# anemo5.net
KiCad netlist of a schematic drawn in EAGLE
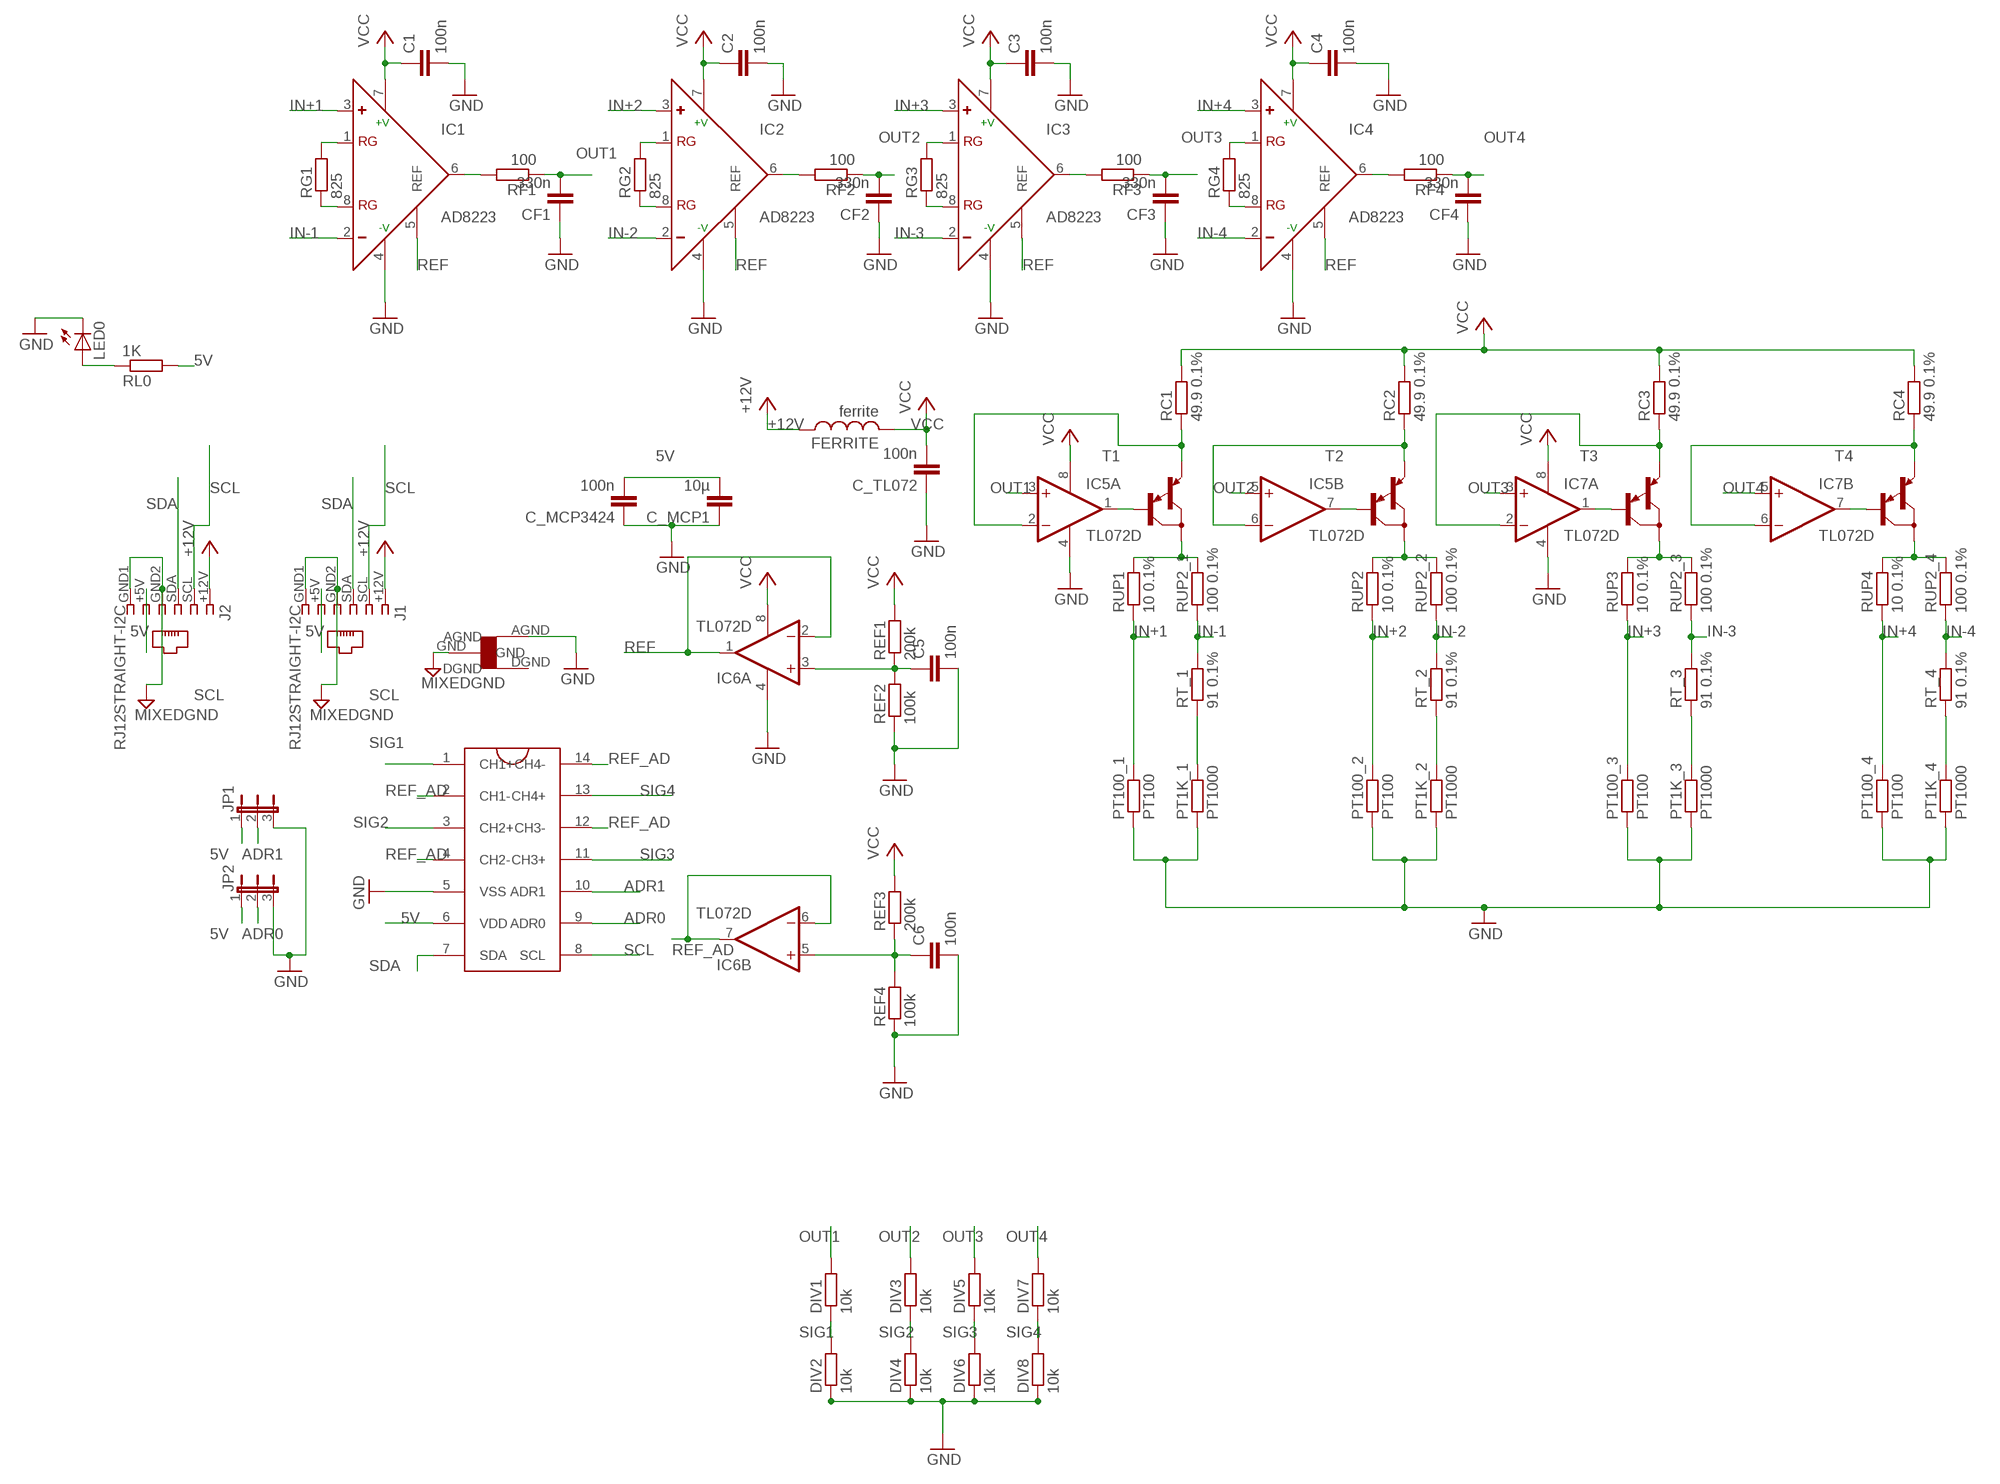
[diagram p0: schematic, sheet 1]

(export (version "E")
  (design (tool "Eeschema 10.0.6"))
  (components
    (comp (ref "C1")
      (value "100n")
      (footprint "eagle-import:C1206")
      (libsource (lib "eagle-import") (part "C-EUC1206"))
    )
    (comp (ref "C2")
      (value "100n")
      (footprint "eagle-import:C1206")
      (libsource (lib "eagle-import") (part "C-EUC1206"))
    )
    (comp (ref "C3")
      (value "100n")
      (footprint "eagle-import:C1206")
      (libsource (lib "eagle-import") (part "C-EUC1206"))
    )
    (comp (ref "C4")
      (value "100n")
      (footprint "eagle-import:C1206")
      (libsource (lib "eagle-import") (part "C-EUC1206"))
    )
    (comp (ref "C5")
      (value "100n")
      (footprint "eagle-import:C1206")
      (libsource (lib "eagle-import") (part "C-EUC1206"))
    )
    (comp (ref "C6")
      (value "100n")
      (footprint "eagle-import:C1206")
      (libsource (lib "eagle-import") (part "C-EUC1206"))
    )
    (comp (ref "CF1")
      (value "330n")
      (footprint "eagle-import:C1206")
      (libsource (lib "eagle-import") (part "C-EUC1206"))
    )
    (comp (ref "CF2")
      (value "330n")
      (footprint "eagle-import:C1206")
      (libsource (lib "eagle-import") (part "C-EUC1206"))
    )
    (comp (ref "CF3")
      (value "330n")
      (footprint "eagle-import:C1206")
      (libsource (lib "eagle-import") (part "C-EUC1206"))
    )
    (comp (ref "CF4")
      (value "330n")
      (footprint "eagle-import:C1206")
      (libsource (lib "eagle-import") (part "C-EUC1206"))
    )
    (comp (ref "C_MCP1")
      (value "10µ")
      (footprint "eagle-import:C1206")
      (libsource (lib "eagle-import") (part "C-EUC1206"))
    )
    (comp (ref "C_MCP3424")
      (value "100n")
      (footprint "eagle-import:C1206")
      (libsource (lib "eagle-import") (part "C-EUC1206"))
    )
    (comp (ref "C_TL072")
      (value "100n")
      (footprint "eagle-import:C1206")
      (libsource (lib "eagle-import") (part "C-EUC1206"))
    )
    (comp (ref "DIV1")
      (value "10k")
      (footprint "eagle-import:M1206")
      (libsource (lib "eagle-import") (part "R-EU_M1206"))
    )
    (comp (ref "DIV2")
      (value "10k")
      (footprint "eagle-import:M1206")
      (libsource (lib "eagle-import") (part "R-EU_M1206"))
    )
    (comp (ref "DIV3")
      (value "10k")
      (footprint "eagle-import:M1206")
      (libsource (lib "eagle-import") (part "R-EU_M1206"))
    )
    (comp (ref "DIV4")
      (value "10k")
      (footprint "eagle-import:M1206")
      (libsource (lib "eagle-import") (part "R-EU_M1206"))
    )
    (comp (ref "DIV5")
      (value "10k")
      (footprint "eagle-import:M1206")
      (libsource (lib "eagle-import") (part "R-EU_M1206"))
    )
    (comp (ref "DIV6")
      (value "10k")
      (footprint "eagle-import:M1206")
      (libsource (lib "eagle-import") (part "R-EU_M1206"))
    )
    (comp (ref "DIV7")
      (value "10k")
      (footprint "eagle-import:M1206")
      (libsource (lib "eagle-import") (part "R-EU_M1206"))
    )
    (comp (ref "DIV8")
      (value "10k")
      (footprint "eagle-import:M1206")
      (libsource (lib "eagle-import") (part "R-EU_M1206"))
    )
    (comp (ref "FERRITE")
      (value "ferrite")
      (footprint "eagle-import:L3216C")
      (libsource (lib "eagle-import") (part "L-USL3216C"))
    )
    (comp (ref "IC1")
      (value "AD8223")
      (footprint "eagle-import:SO8")
      (fields (field (name "MPN") "AD620AR"))
      (libsource (lib "eagle-import") (part "AD620R"))
    )
    (comp (ref "IC2")
      (value "AD8223")
      (footprint "eagle-import:SO8")
      (fields (field (name "MPN") "AD620AR"))
      (libsource (lib "eagle-import") (part "AD620R"))
    )
    (comp (ref "IC3")
      (value "AD8223")
      (footprint "eagle-import:SO8")
      (fields (field (name "MPN") "AD620AR"))
      (libsource (lib "eagle-import") (part "AD620R"))
    )
    (comp (ref "IC4")
      (value "AD8223")
      (footprint "eagle-import:SO8")
      (fields (field (name "MPN") "AD620AR"))
      (libsource (lib "eagle-import") (part "AD620R"))
    )
    (comp (ref "IC5")
      (value "TL072D")
      (footprint "eagle-import:SO08")
      (libsource (lib "eagle-import") (part "TL072D"))
    )
    (comp (ref "IC6")
      (value "TL072D")
      (footprint "eagle-import:SO08")
      (libsource (lib "eagle-import") (part "TL072D"))
    )
    (comp (ref "IC7")
      (value "TL072D")
      (footprint "eagle-import:SO08")
      (libsource (lib "eagle-import") (part "TL072D"))
    )
    (comp (ref "J1")
      (value "RJ12STRAIGHT-I2C")
      (footprint "eagle-import:RJ12-STRAIGHT-I2C")
      (libsource (lib "eagle-import") (part "RJ12STRAIGHT-I2C"))
    )
    (comp (ref "J2")
      (value "RJ12STRAIGHT-I2C")
      (footprint "eagle-import:RJ12-STRAIGHT-I2C")
      (libsource (lib "eagle-import") (part "RJ12STRAIGHT-I2C"))
    )
    (comp (ref "JP1")
      (value "JP2E")
      (footprint "eagle-import:JP2")
      (libsource (lib "eagle-import") (part "JP2E"))
    )
    (comp (ref "JP2")
      (value "JP2E")
      (footprint "eagle-import:JP2")
      (libsource (lib "eagle-import") (part "JP2E"))
    )
    (comp (ref "LED0")
      (value "LED1206")
      (footprint "eagle-import:LED-1206")
      (libsource (lib "eagle-import") (part "LED1206"))
    )
    (comp (ref "PT1K_1")
      (value "PT1000")
      (footprint "eagle-import:M1206")
      (libsource (lib "eagle-import") (part "R-EU_M1206"))
    )
    (comp (ref "PT1K_2")
      (value "PT1000")
      (footprint "eagle-import:M1206")
      (libsource (lib "eagle-import") (part "R-EU_M1206"))
    )
    (comp (ref "PT1K_3")
      (value "PT1000")
      (footprint "eagle-import:M1206")
      (libsource (lib "eagle-import") (part "R-EU_M1206"))
    )
    (comp (ref "PT1K_4")
      (value "PT1000")
      (footprint "eagle-import:M1206")
      (libsource (lib "eagle-import") (part "R-EU_M1206"))
    )
    (comp (ref "PT100_1")
      (value "PT100")
      (footprint "eagle-import:M1206")
      (libsource (lib "eagle-import") (part "R-EU_M1206"))
    )
    (comp (ref "PT100_2")
      (value "PT100")
      (footprint "eagle-import:M1206")
      (libsource (lib "eagle-import") (part "R-EU_M1206"))
    )
    (comp (ref "PT100_3")
      (value "PT100")
      (footprint "eagle-import:M1206")
      (libsource (lib "eagle-import") (part "R-EU_M1206"))
    )
    (comp (ref "PT100_4")
      (value "PT100")
      (footprint "eagle-import:M1206")
      (libsource (lib "eagle-import") (part "R-EU_M1206"))
    )
    (comp (ref "RC1")
      (value "49.9 0.1%")
      (footprint "eagle-import:M1206")
      (libsource (lib "eagle-import") (part "R-EU_M1206"))
    )
    (comp (ref "RC2")
      (value "49.9 0.1%")
      (footprint "eagle-import:M1206")
      (libsource (lib "eagle-import") (part "R-EU_M1206"))
    )
    (comp (ref "RC3")
      (value "49.9 0.1%")
      (footprint "eagle-import:M1206")
      (libsource (lib "eagle-import") (part "R-EU_M1206"))
    )
    (comp (ref "RC4")
      (value "49.9 0.1%")
      (footprint "eagle-import:M1206")
      (libsource (lib "eagle-import") (part "R-EU_M1206"))
    )
    (comp (ref "REF1")
      (value "200k")
      (footprint "eagle-import:M1206")
      (libsource (lib "eagle-import") (part "R-EU_M1206"))
    )
    (comp (ref "REF2")
      (value "100k")
      (footprint "eagle-import:M1206")
      (libsource (lib "eagle-import") (part "R-EU_M1206"))
    )
    (comp (ref "REF3")
      (value "200k")
      (footprint "eagle-import:M1206")
      (libsource (lib "eagle-import") (part "R-EU_M1206"))
    )
    (comp (ref "REF4")
      (value "100k")
      (footprint "eagle-import:M1206")
      (libsource (lib "eagle-import") (part "R-EU_M1206"))
    )
    (comp (ref "RF1")
      (value "100")
      (footprint "eagle-import:M1206")
      (libsource (lib "eagle-import") (part "R-EU_M1206"))
    )
    (comp (ref "RF2")
      (value "100")
      (footprint "eagle-import:M1206")
      (libsource (lib "eagle-import") (part "R-EU_M1206"))
    )
    (comp (ref "RF3")
      (value "100")
      (footprint "eagle-import:M1206")
      (libsource (lib "eagle-import") (part "R-EU_M1206"))
    )
    (comp (ref "RF4")
      (value "100")
      (footprint "eagle-import:M1206")
      (libsource (lib "eagle-import") (part "R-EU_M1206"))
    )
    (comp (ref "RG1")
      (value "825")
      (footprint "eagle-import:M1206")
      (libsource (lib "eagle-import") (part "R-EU_M1206"))
    )
    (comp (ref "RG2")
      (value "825")
      (footprint "eagle-import:M1206")
      (libsource (lib "eagle-import") (part "R-EU_M1206"))
    )
    (comp (ref "RG3")
      (value "825")
      (footprint "eagle-import:M1206")
      (libsource (lib "eagle-import") (part "R-EU_M1206"))
    )
    (comp (ref "RG4")
      (value "825")
      (footprint "eagle-import:M1206")
      (libsource (lib "eagle-import") (part "R-EU_M1206"))
    )
    (comp (ref "RL0")
      (value "1K")
      (footprint "eagle-import:M1206")
      (libsource (lib "eagle-import") (part "R-EU_M1206"))
    )
    (comp (ref "RT_1")
      (value "91 0.1%")
      (footprint "eagle-import:M1206")
      (libsource (lib "eagle-import") (part "R-EU_M1206"))
    )
    (comp (ref "RT_2")
      (value "91 0.1%")
      (footprint "eagle-import:M1206")
      (libsource (lib "eagle-import") (part "R-EU_M1206"))
    )
    (comp (ref "RT_3")
      (value "91 0.1%")
      (footprint "eagle-import:M1206")
      (libsource (lib "eagle-import") (part "R-EU_M1206"))
    )
    (comp (ref "RT_4")
      (value "91 0.1%")
      (footprint "eagle-import:M1206")
      (libsource (lib "eagle-import") (part "R-EU_M1206"))
    )
    (comp (ref "RUP1")
      (value "10 0.1%")
      (footprint "eagle-import:M1206")
      (libsource (lib "eagle-import") (part "R-EU_M1206"))
    )
    (comp (ref "RUP2")
      (value "10 0.1%")
      (footprint "eagle-import:M1206")
      (libsource (lib "eagle-import") (part "R-EU_M1206"))
    )
    (comp (ref "RUP2_1")
      (value "100 0.1%")
      (footprint "eagle-import:M1206")
      (libsource (lib "eagle-import") (part "R-EU_M1206"))
    )
    (comp (ref "RUP2_2")
      (value "100 0.1%")
      (footprint "eagle-import:M1206")
      (libsource (lib "eagle-import") (part "R-EU_M1206"))
    )
    (comp (ref "RUP2_3")
      (value "100 0.1%")
      (footprint "eagle-import:M1206")
      (libsource (lib "eagle-import") (part "R-EU_M1206"))
    )
    (comp (ref "RUP2_4")
      (value "100 0.1%")
      (footprint "eagle-import:M1206")
      (libsource (lib "eagle-import") (part "R-EU_M1206"))
    )
    (comp (ref "RUP3")
      (value "10 0.1%")
      (footprint "eagle-import:M1206")
      (libsource (lib "eagle-import") (part "R-EU_M1206"))
    )
    (comp (ref "RUP4")
      (value "10 0.1%")
      (footprint "eagle-import:M1206")
      (libsource (lib "eagle-import") (part "R-EU_M1206"))
    )
    (comp (ref "T1")
      (value "MMBTA64LT1-PNP_DARL-SOT23-BEC")
      (footprint "eagle-import:SOT23-BEC")
      (libsource (lib "eagle-import") (part "-PNP_DARL-SOT23-BECMMBTA64LT1"))
    )
    (comp (ref "T2")
      (value "MMBTA64LT1-PNP_DARL-SOT23-BEC")
      (footprint "eagle-import:SOT23-BEC")
      (libsource (lib "eagle-import") (part "-PNP_DARL-SOT23-BECMMBTA64LT1"))
    )
    (comp (ref "T3")
      (value "MMBTA64LT1-PNP_DARL-SOT23-BEC")
      (footprint "eagle-import:SOT23-BEC")
      (libsource (lib "eagle-import") (part "-PNP_DARL-SOT23-BECMMBTA64LT1"))
    )
    (comp (ref "T4")
      (value "MMBTA64LT1-PNP_DARL-SOT23-BEC")
      (footprint "eagle-import:SOT23-BEC")
      (libsource (lib "eagle-import") (part "-PNP_DARL-SOT23-BECMMBTA64LT1"))
    )
    (comp (ref "U$1")
      (value "MCP3424(SO14)")
      (footprint "eagle-import:14LDSOIC")
      (libsource (lib "eagle-import") (part "MCP3424(SO14)"))
    )
    (comp (ref "U$2")
      (value "STARGND")
      (footprint "eagle-import:STAR")
      (libsource (lib "eagle-import") (part "STARGND"))
    )
  )
  (nets
    (net (code "1") (name "+12V") (class "Default")
      (node (ref "FERRITE") (pin "1") (pinfunction "1_1") (pintype "passive"))
      (node (ref "J1") (pin "+12V") (pinfunction "1_+12V") (pintype "bidirectional"))
      (node (ref "J2") (pin "+12V") (pinfunction "1_+12V") (pintype "bidirectional"))
    )
    (net (code "2") (name "/5V") (class "Default")
      (node (ref "C_MCP1") (pin "2") (pinfunction "2_2") (pintype "passive"))
      (node (ref "C_MCP3424") (pin "2") (pinfunction "2_2") (pintype "passive"))
      (node (ref "J1") (pin "+5V") (pinfunction "5_+5V") (pintype "bidirectional"))
      (node (ref "J2") (pin "+5V") (pinfunction "5_+5V") (pintype "bidirectional"))
      (node (ref "JP1") (pin "1") (pinfunction "1_1") (pintype "passive"))
      (node (ref "JP2") (pin "1") (pinfunction "1_1") (pintype "passive"))
      (node (ref "RL0") (pin "2") (pinfunction "2_2") (pintype "passive"))
      (node (ref "U$1") (pin "6") (pinfunction "VDD_6") (pintype "bidirectional"))
    )
    (net (code "3") (name "/ADR0") (class "Default")
      (node (ref "JP2") (pin "2") (pinfunction "2_2") (pintype "passive"))
      (node (ref "U$1") (pin "9") (pinfunction "ADR0_9") (pintype "bidirectional"))
    )
    (net (code "4") (name "/ADR1") (class "Default")
      (node (ref "JP1") (pin "2") (pinfunction "2_2") (pintype "passive"))
      (node (ref "U$1") (pin "10") (pinfunction "ADR1_10") (pintype "bidirectional"))
    )
    (net (code "5") (name "/IN+1") (class "Default")
      (node (ref "IC1") (pin "3") (pinfunction "+_3") (pintype "input"))
      (node (ref "PT100_1") (pin "2") (pinfunction "2_2") (pintype "passive"))
      (node (ref "RUP1") (pin "1") (pinfunction "1_1") (pintype "passive"))
    )
    (net (code "6") (name "/IN+2") (class "Default")
      (node (ref "IC2") (pin "3") (pinfunction "+_3") (pintype "input"))
      (node (ref "PT100_2") (pin "2") (pinfunction "2_2") (pintype "passive"))
      (node (ref "RUP2") (pin "1") (pinfunction "1_1") (pintype "passive"))
    )
    (net (code "7") (name "/IN+3") (class "Default")
      (node (ref "IC3") (pin "3") (pinfunction "+_3") (pintype "input"))
      (node (ref "PT100_3") (pin "2") (pinfunction "2_2") (pintype "passive"))
      (node (ref "RUP3") (pin "1") (pinfunction "1_1") (pintype "passive"))
    )
    (net (code "8") (name "/IN+4") (class "Default")
      (node (ref "IC4") (pin "3") (pinfunction "+_3") (pintype "input"))
      (node (ref "PT100_4") (pin "2") (pinfunction "2_2") (pintype "passive"))
      (node (ref "RUP4") (pin "1") (pinfunction "1_1") (pintype "passive"))
    )
    (net (code "9") (name "/IN-1") (class "Default")
      (node (ref "IC1") (pin "2") (pinfunction "-_2") (pintype "input"))
      (node (ref "RT_1") (pin "2") (pinfunction "2_2") (pintype "passive"))
      (node (ref "RUP2_1") (pin "1") (pinfunction "1_1") (pintype "passive"))
    )
    (net (code "10") (name "/IN-2") (class "Default")
      (node (ref "IC2") (pin "2") (pinfunction "-_2") (pintype "input"))
      (node (ref "RT_2") (pin "2") (pinfunction "2_2") (pintype "passive"))
      (node (ref "RUP2_2") (pin "1") (pinfunction "1_1") (pintype "passive"))
    )
    (net (code "11") (name "/IN-3") (class "Default")
      (node (ref "IC3") (pin "2") (pinfunction "-_2") (pintype "input"))
      (node (ref "RT_3") (pin "2") (pinfunction "2_2") (pintype "passive"))
      (node (ref "RUP2_3") (pin "1") (pinfunction "1_1") (pintype "passive"))
    )
    (net (code "12") (name "/IN-4") (class "Default")
      (node (ref "IC4") (pin "2") (pinfunction "-_2") (pintype "input"))
      (node (ref "RT_4") (pin "2") (pinfunction "2_2") (pintype "passive"))
      (node (ref "RUP2_4") (pin "1") (pinfunction "1_1") (pintype "passive"))
    )
    (net (code "13") (name "/OUT1") (class "Default")
      (node (ref "CF1") (pin "2") (pinfunction "2_2") (pintype "passive"))
      (node (ref "DIV1") (pin "2") (pinfunction "2_2") (pintype "passive"))
      (node (ref "IC5") (pin "3") (pinfunction "+IN_3") (pintype "input"))
      (node (ref "RF1") (pin "1") (pinfunction "1_1") (pintype "passive"))
    )
    (net (code "14") (name "/OUT2") (class "Default")
      (node (ref "CF2") (pin "2") (pinfunction "2_2") (pintype "passive"))
      (node (ref "DIV3") (pin "2") (pinfunction "2_2") (pintype "passive"))
      (node (ref "IC5") (pin "5") (pinfunction "+IN_5") (pintype "input"))
      (node (ref "RF2") (pin "1") (pinfunction "1_1") (pintype "passive"))
    )
    (net (code "15") (name "/OUT3") (class "Default")
      (node (ref "CF3") (pin "2") (pinfunction "2_2") (pintype "passive"))
      (node (ref "DIV5") (pin "2") (pinfunction "2_2") (pintype "passive"))
      (node (ref "IC7") (pin "3") (pinfunction "+IN_3") (pintype "input"))
      (node (ref "RF3") (pin "1") (pinfunction "1_1") (pintype "passive"))
    )
    (net (code "16") (name "/OUT4") (class "Default")
      (node (ref "CF4") (pin "2") (pinfunction "2_2") (pintype "passive"))
      (node (ref "DIV7") (pin "2") (pinfunction "2_2") (pintype "passive"))
      (node (ref "IC7") (pin "5") (pinfunction "+IN_5") (pintype "input"))
      (node (ref "RF4") (pin "1") (pinfunction "1_1") (pintype "passive"))
    )
    (net (code "17") (name "/REF") (class "Default")
      (node (ref "IC1") (pin "5") (pinfunction "REF_5") (pintype "passive"))
      (node (ref "IC2") (pin "5") (pinfunction "REF_5") (pintype "passive"))
      (node (ref "IC3") (pin "5") (pinfunction "REF_5") (pintype "passive"))
      (node (ref "IC4") (pin "5") (pinfunction "REF_5") (pintype "passive"))
      (node (ref "IC6") (pin "1") (pinfunction "OUT_1") (pintype "output"))
      (node (ref "IC6") (pin "2") (pinfunction "-IN_2") (pintype "input"))
    )
    (net (code "18") (name "/REF_AD") (class "Default")
      (node (ref "IC6") (pin "6") (pinfunction "-IN_6") (pintype "input"))
      (node (ref "IC6") (pin "7") (pinfunction "OUT_7") (pintype "output"))
      (node (ref "U$1") (pin "12") (pinfunction "CH3-_12") (pintype "bidirectional"))
      (node (ref "U$1") (pin "14") (pinfunction "CH4-_14") (pintype "bidirectional"))
      (node (ref "U$1") (pin "2") (pinfunction "CH1-_2") (pintype "bidirectional"))
      (node (ref "U$1") (pin "4") (pinfunction "CH2-_4") (pintype "bidirectional"))
    )
    (net (code "19") (name "/SCL") (class "Default")
      (node (ref "J1") (pin "SCL") (pinfunction "2_SCL") (pintype "bidirectional"))
      (node (ref "J2") (pin "SCL") (pinfunction "2_SCL") (pintype "bidirectional"))
      (node (ref "U$1") (pin "8") (pinfunction "SCL_8") (pintype "bidirectional"))
    )
    (net (code "20") (name "/SDA") (class "Default")
      (node (ref "J1") (pin "SDA") (pinfunction "3_SDA") (pintype "bidirectional"))
      (node (ref "J2") (pin "SDA") (pinfunction "3_SDA") (pintype "bidirectional"))
      (node (ref "U$1") (pin "7") (pinfunction "SDA_7") (pintype "bidirectional"))
    )
    (net (code "21") (name "/SIG1") (class "Default")
      (node (ref "DIV1") (pin "1") (pinfunction "1_1") (pintype "passive"))
      (node (ref "DIV2") (pin "2") (pinfunction "2_2") (pintype "passive"))
      (node (ref "U$1") (pin "1") (pinfunction "CH1+_1") (pintype "bidirectional"))
    )
    (net (code "22") (name "/SIG2") (class "Default")
      (node (ref "DIV3") (pin "1") (pinfunction "1_1") (pintype "passive"))
      (node (ref "DIV4") (pin "2") (pinfunction "2_2") (pintype "passive"))
      (node (ref "U$1") (pin "3") (pinfunction "CH2+_3") (pintype "bidirectional"))
    )
    (net (code "23") (name "/SIG3") (class "Default")
      (node (ref "DIV5") (pin "1") (pinfunction "1_1") (pintype "passive"))
      (node (ref "DIV6") (pin "2") (pinfunction "2_2") (pintype "passive"))
      (node (ref "U$1") (pin "11") (pinfunction "CH3+_11") (pintype "bidirectional"))
    )
    (net (code "24") (name "/SIG4") (class "Default")
      (node (ref "DIV7") (pin "1") (pinfunction "1_1") (pintype "passive"))
      (node (ref "DIV8") (pin "2") (pinfunction "2_2") (pintype "passive"))
      (node (ref "U$1") (pin "13") (pinfunction "CH4+_13") (pintype "bidirectional"))
    )
    (net (code "25") (name "GND") (class "Default")
      (node (ref "C1") (pin "2") (pinfunction "2_2") (pintype "passive"))
      (node (ref "C2") (pin "2") (pinfunction "2_2") (pintype "passive"))
      (node (ref "C3") (pin "2") (pinfunction "2_2") (pintype "passive"))
      (node (ref "C4") (pin "2") (pinfunction "2_2") (pintype "passive"))
      (node (ref "C5") (pin "2") (pinfunction "2_2") (pintype "passive"))
      (node (ref "C6") (pin "2") (pinfunction "2_2") (pintype "passive"))
      (node (ref "CF1") (pin "1") (pinfunction "1_1") (pintype "passive"))
      (node (ref "CF2") (pin "1") (pinfunction "1_1") (pintype "passive"))
      (node (ref "CF3") (pin "1") (pinfunction "1_1") (pintype "passive"))
      (node (ref "CF4") (pin "1") (pinfunction "1_1") (pintype "passive"))
      (node (ref "C_MCP1") (pin "1") (pinfunction "1_1") (pintype "passive"))
      (node (ref "C_MCP3424") (pin "1") (pinfunction "1_1") (pintype "passive"))
      (node (ref "C_TL072") (pin "1") (pinfunction "1_1") (pintype "passive"))
      (node (ref "DIV2") (pin "1") (pinfunction "1_1") (pintype "passive"))
      (node (ref "DIV4") (pin "1") (pinfunction "1_1") (pintype "passive"))
      (node (ref "DIV6") (pin "1") (pinfunction "1_1") (pintype "passive"))
      (node (ref "DIV8") (pin "1") (pinfunction "1_1") (pintype "passive"))
      (node (ref "IC1") (pin "4") (pinfunction "-V_4") (pintype "power_in"))
      (node (ref "IC2") (pin "4") (pinfunction "-V_4") (pintype "power_in"))
      (node (ref "IC3") (pin "4") (pinfunction "-V_4") (pintype "power_in"))
      (node (ref "IC4") (pin "4") (pinfunction "-V_4") (pintype "power_in"))
      (node (ref "IC5") (pin "4") (pinfunction "V-_4") (pintype "power_in"))
      (node (ref "IC6") (pin "4") (pinfunction "V-_4") (pintype "power_in"))
      (node (ref "IC7") (pin "4") (pinfunction "V-_4") (pintype "power_in"))
      (node (ref "JP1") (pin "3") (pinfunction "3_3") (pintype "passive"))
      (node (ref "JP2") (pin "3") (pinfunction "3_3") (pintype "passive"))
      (node (ref "LED0") (pin "C") (pinfunction "C_C") (pintype "passive"))
      (node (ref "PT100_1") (pin "1") (pinfunction "1_1") (pintype "passive"))
      (node (ref "PT100_2") (pin "1") (pinfunction "1_1") (pintype "passive"))
      (node (ref "PT100_3") (pin "1") (pinfunction "1_1") (pintype "passive"))
      (node (ref "PT100_4") (pin "1") (pinfunction "1_1") (pintype "passive"))
      (node (ref "PT1K_1") (pin "1") (pinfunction "1_1") (pintype "passive"))
      (node (ref "PT1K_2") (pin "1") (pinfunction "1_1") (pintype "passive"))
      (node (ref "PT1K_3") (pin "1") (pinfunction "1_1") (pintype "passive"))
      (node (ref "PT1K_4") (pin "1") (pinfunction "1_1") (pintype "passive"))
      (node (ref "REF2") (pin "1") (pinfunction "1_1") (pintype "passive"))
      (node (ref "REF4") (pin "1") (pinfunction "1_1") (pintype "passive"))
      (node (ref "U$1") (pin "5") (pinfunction "VSS_5") (pintype "bidirectional"))
      (node (ref "U$2") (pin "AGND") (pinfunction "AGND_AGND") (pintype "output"))
    )
    (net (code "26") (name "MIXEDGND") (class "Default")
      (node (ref "J1") (pin "GND1") (pinfunction "6_GND1") (pintype "bidirectional"))
      (node (ref "J1") (pin "GND2") (pinfunction "4_GND2") (pintype "bidirectional"))
      (node (ref "J2") (pin "GND1") (pinfunction "6_GND1") (pintype "bidirectional"))
      (node (ref "J2") (pin "GND2") (pinfunction "4_GND2") (pintype "bidirectional"))
      (node (ref "U$2") (pin "GND") (pinfunction "GND_GND") (pintype "power_in"))
    )
    (net (code "27") (name "Net-(IC1-OUT)") (class "Default")
      (node (ref "IC1") (pin "6") (pinfunction "OUT_6") (pintype "output"))
      (node (ref "RF1") (pin "2") (pinfunction "2_2") (pintype "passive"))
    )
    (net (code "28") (name "Net-(IC1-RG-Pad1)") (class "Default")
      (node (ref "IC1") (pin "1") (pinfunction "RG_1") (pintype "passive"))
      (node (ref "RG1") (pin "2") (pinfunction "2_2") (pintype "passive"))
    )
    (net (code "29") (name "Net-(IC1-RG-Pad8)") (class "Default")
      (node (ref "IC1") (pin "8") (pinfunction "RG_8") (pintype "passive"))
      (node (ref "RG1") (pin "1") (pinfunction "1_1") (pintype "passive"))
    )
    (net (code "30") (name "Net-(IC2-OUT)") (class "Default")
      (node (ref "IC2") (pin "6") (pinfunction "OUT_6") (pintype "output"))
      (node (ref "RF2") (pin "2") (pinfunction "2_2") (pintype "passive"))
    )
    (net (code "31") (name "Net-(IC2-RG-Pad1)") (class "Default")
      (node (ref "IC2") (pin "1") (pinfunction "RG_1") (pintype "passive"))
      (node (ref "RG2") (pin "2") (pinfunction "2_2") (pintype "passive"))
    )
    (net (code "32") (name "Net-(IC2-RG-Pad8)") (class "Default")
      (node (ref "IC2") (pin "8") (pinfunction "RG_8") (pintype "passive"))
      (node (ref "RG2") (pin "1") (pinfunction "1_1") (pintype "passive"))
    )
    (net (code "33") (name "Net-(IC3-OUT)") (class "Default")
      (node (ref "IC3") (pin "6") (pinfunction "OUT_6") (pintype "output"))
      (node (ref "RF3") (pin "2") (pinfunction "2_2") (pintype "passive"))
    )
    (net (code "34") (name "Net-(IC3-RG-Pad1)") (class "Default")
      (node (ref "IC3") (pin "1") (pinfunction "RG_1") (pintype "passive"))
      (node (ref "RG3") (pin "2") (pinfunction "2_2") (pintype "passive"))
    )
    (net (code "35") (name "Net-(IC3-RG-Pad8)") (class "Default")
      (node (ref "IC3") (pin "8") (pinfunction "RG_8") (pintype "passive"))
      (node (ref "RG3") (pin "1") (pinfunction "1_1") (pintype "passive"))
    )
    (net (code "36") (name "Net-(IC4-OUT)") (class "Default")
      (node (ref "IC4") (pin "6") (pinfunction "OUT_6") (pintype "output"))
      (node (ref "RF4") (pin "2") (pinfunction "2_2") (pintype "passive"))
    )
    (net (code "37") (name "Net-(IC4-RG-Pad1)") (class "Default")
      (node (ref "IC4") (pin "1") (pinfunction "RG_1") (pintype "passive"))
      (node (ref "RG4") (pin "2") (pinfunction "2_2") (pintype "passive"))
    )
    (net (code "38") (name "Net-(IC4-RG-Pad8)") (class "Default")
      (node (ref "IC4") (pin "8") (pinfunction "RG_8") (pintype "passive"))
      (node (ref "RG4") (pin "1") (pinfunction "1_1") (pintype "passive"))
    )
    (net (code "39") (name "Net-(IC5A--IN)") (class "Default")
      (node (ref "IC5") (pin "2") (pinfunction "-IN_2") (pintype "input"))
      (node (ref "RC1") (pin "1") (pinfunction "1_1") (pintype "passive"))
      (node (ref "T1") (pin "E") (pinfunction "E_E") (pintype "passive"))
    )
    (net (code "40") (name "Net-(IC5A-OUT)") (class "Default")
      (node (ref "IC5") (pin "1") (pinfunction "OUT_1") (pintype "output"))
      (node (ref "T1") (pin "B") (pinfunction "B_B") (pintype "passive"))
    )
    (net (code "41") (name "Net-(IC5B--IN)") (class "Default")
      (node (ref "IC5") (pin "6") (pinfunction "-IN_6") (pintype "input"))
      (node (ref "RC2") (pin "1") (pinfunction "1_1") (pintype "passive"))
      (node (ref "T2") (pin "E") (pinfunction "E_E") (pintype "passive"))
    )
    (net (code "42") (name "Net-(IC5B-OUT)") (class "Default")
      (node (ref "IC5") (pin "7") (pinfunction "OUT_7") (pintype "output"))
      (node (ref "T2") (pin "B") (pinfunction "B_B") (pintype "passive"))
    )
    (net (code "43") (name "Net-(IC6A-+IN)") (class "Default")
      (node (ref "C5") (pin "1") (pinfunction "1_1") (pintype "passive"))
      (node (ref "IC6") (pin "3") (pinfunction "+IN_3") (pintype "input"))
      (node (ref "REF1") (pin "1") (pinfunction "1_1") (pintype "passive"))
      (node (ref "REF2") (pin "2") (pinfunction "2_2") (pintype "passive"))
    )
    (net (code "44") (name "Net-(IC6B-+IN)") (class "Default")
      (node (ref "C6") (pin "1") (pinfunction "1_1") (pintype "passive"))
      (node (ref "IC6") (pin "5") (pinfunction "+IN_5") (pintype "input"))
      (node (ref "REF3") (pin "1") (pinfunction "1_1") (pintype "passive"))
      (node (ref "REF4") (pin "2") (pinfunction "2_2") (pintype "passive"))
    )
    (net (code "45") (name "Net-(IC7A--IN)") (class "Default")
      (node (ref "IC7") (pin "2") (pinfunction "-IN_2") (pintype "input"))
      (node (ref "RC3") (pin "1") (pinfunction "1_1") (pintype "passive"))
      (node (ref "T3") (pin "E") (pinfunction "E_E") (pintype "passive"))
    )
    (net (code "46") (name "Net-(IC7A-OUT)") (class "Default")
      (node (ref "IC7") (pin "1") (pinfunction "OUT_1") (pintype "output"))
      (node (ref "T3") (pin "B") (pinfunction "B_B") (pintype "passive"))
    )
    (net (code "47") (name "Net-(IC7B--IN)") (class "Default")
      (node (ref "IC7") (pin "6") (pinfunction "-IN_6") (pintype "input"))
      (node (ref "RC4") (pin "1") (pinfunction "1_1") (pintype "passive"))
      (node (ref "T4") (pin "E") (pinfunction "E_E") (pintype "passive"))
    )
    (net (code "48") (name "Net-(IC7B-OUT)") (class "Default")
      (node (ref "IC7") (pin "7") (pinfunction "OUT_7") (pintype "output"))
      (node (ref "T4") (pin "B") (pinfunction "B_B") (pintype "passive"))
    )
    (net (code "49") (name "Net-(LED0-PadA)") (class "Default")
      (node (ref "LED0") (pin "A") (pinfunction "A_A") (pintype "passive"))
      (node (ref "RL0") (pin "1") (pinfunction "1_1") (pintype "passive"))
    )
    (net (code "50") (name "Net-(PT1K_1-Pad2)") (class "Default")
      (node (ref "PT1K_1") (pin "2") (pinfunction "2_2") (pintype "passive"))
      (node (ref "RT_1") (pin "1") (pinfunction "1_1") (pintype "passive"))
    )
    (net (code "51") (name "Net-(PT1K_2-Pad2)") (class "Default")
      (node (ref "PT1K_2") (pin "2") (pinfunction "2_2") (pintype "passive"))
      (node (ref "RT_2") (pin "1") (pinfunction "1_1") (pintype "passive"))
    )
    (net (code "52") (name "Net-(PT1K_3-Pad2)") (class "Default")
      (node (ref "PT1K_3") (pin "2") (pinfunction "2_2") (pintype "passive"))
      (node (ref "RT_3") (pin "1") (pinfunction "1_1") (pintype "passive"))
    )
    (net (code "53") (name "Net-(PT1K_4-Pad2)") (class "Default")
      (node (ref "PT1K_4") (pin "2") (pinfunction "2_2") (pintype "passive"))
      (node (ref "RT_4") (pin "1") (pinfunction "1_1") (pintype "passive"))
    )
    (net (code "54") (name "Net-(RUP1-Pad2)") (class "Default")
      (node (ref "RUP1") (pin "2") (pinfunction "2_2") (pintype "passive"))
      (node (ref "RUP2_1") (pin "2") (pinfunction "2_2") (pintype "passive"))
      (node (ref "T1") (pin "C") (pinfunction "C_C") (pintype "passive"))
    )
    (net (code "55") (name "Net-(RUP2-Pad2)") (class "Default")
      (node (ref "RUP2") (pin "2") (pinfunction "2_2") (pintype "passive"))
      (node (ref "RUP2_2") (pin "2") (pinfunction "2_2") (pintype "passive"))
      (node (ref "T2") (pin "C") (pinfunction "C_C") (pintype "passive"))
    )
    (net (code "56") (name "Net-(RUP2_3-Pad2)") (class "Default")
      (node (ref "RUP2_3") (pin "2") (pinfunction "2_2") (pintype "passive"))
      (node (ref "RUP3") (pin "2") (pinfunction "2_2") (pintype "passive"))
      (node (ref "T3") (pin "C") (pinfunction "C_C") (pintype "passive"))
    )
    (net (code "57") (name "Net-(RUP2_4-Pad2)") (class "Default")
      (node (ref "RUP2_4") (pin "2") (pinfunction "2_2") (pintype "passive"))
      (node (ref "RUP4") (pin "2") (pinfunction "2_2") (pintype "passive"))
      (node (ref "T4") (pin "C") (pinfunction "C_C") (pintype "passive"))
    )
    (net (code "58") (name "VCC") (class "Default")
      (node (ref "C1") (pin "1") (pinfunction "1_1") (pintype "passive"))
      (node (ref "C2") (pin "1") (pinfunction "1_1") (pintype "passive"))
      (node (ref "C3") (pin "1") (pinfunction "1_1") (pintype "passive"))
      (node (ref "C4") (pin "1") (pinfunction "1_1") (pintype "passive"))
      (node (ref "C_TL072") (pin "2") (pinfunction "2_2") (pintype "passive"))
      (node (ref "FERRITE") (pin "2") (pinfunction "2_2") (pintype "passive"))
      (node (ref "IC1") (pin "7") (pinfunction "+V_7") (pintype "power_in"))
      (node (ref "IC2") (pin "7") (pinfunction "+V_7") (pintype "power_in"))
      (node (ref "IC3") (pin "7") (pinfunction "+V_7") (pintype "power_in"))
      (node (ref "IC4") (pin "7") (pinfunction "+V_7") (pintype "power_in"))
      (node (ref "IC5") (pin "8") (pinfunction "V+_8") (pintype "power_in"))
      (node (ref "IC6") (pin "8") (pinfunction "V+_8") (pintype "power_in"))
      (node (ref "IC7") (pin "8") (pinfunction "V+_8") (pintype "power_in"))
      (node (ref "RC1") (pin "2") (pinfunction "2_2") (pintype "passive"))
      (node (ref "RC2") (pin "2") (pinfunction "2_2") (pintype "passive"))
      (node (ref "RC3") (pin "2") (pinfunction "2_2") (pintype "passive"))
      (node (ref "RC4") (pin "2") (pinfunction "2_2") (pintype "passive"))
      (node (ref "REF1") (pin "2") (pinfunction "2_2") (pintype "passive"))
      (node (ref "REF3") (pin "2") (pinfunction "2_2") (pintype "passive"))
    )
    (net (code "59") (name "unconnected-(U$2-PadDGND)") (class "Default")
      (node (ref "U$2") (pin "DGND") (pinfunction "DGND_DGND") (pintype "output"))
    )
  )
)
